# IMU_MPU9250.net
KiCad netlist of a schematic drawn in Altium Designer
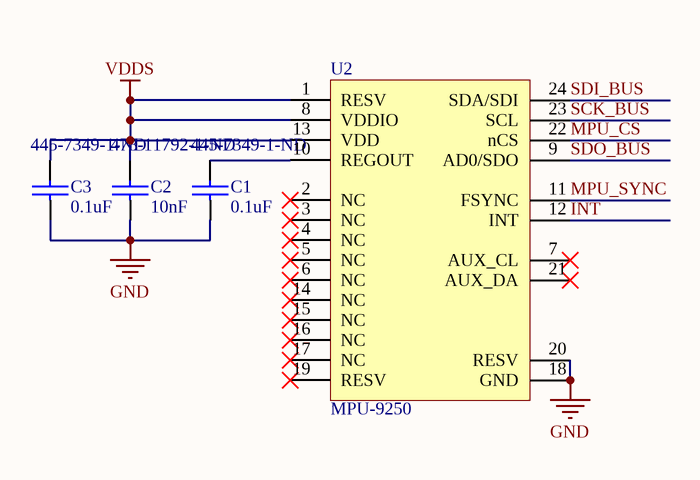
[diagram p0: IMU_MPU9250.SchDoc]

(export (version "E")
  (design (tool "Eeschema 10.0.6"))
  (components
    (comp (ref "C1")
      (value "0.1uF")
      (footprint "0402[IMP]")
      (fields (field (name "VOLTAGE") "CMAX") (field (name "SUPPLIER PART NUMBER 1") "445-7349-1-ND"))
      (libsource (lib "Biosense_Altium_Library") (part "CAPACITOR"))
    )
    (comp (ref "C2")
      (value "10nF")
      (footprint "0402[IMP]")
      (fields (field (name "VOLTAGE") "CMAX") (field (name "SUPPLIER PART NUMBER 1") "478-11792-1-ND"))
      (libsource (lib "Biosense_Altium_Library") (part "CAPACITOR"))
    )
    (comp (ref "C3")
      (value "0.1uF")
      (footprint "0402[IMP]")
      (fields (field (name "VOLTAGE") "CMAX") (field (name "SUPPLIER PART NUMBER 1") "445-7349-1-ND"))
      (libsource (lib "Biosense_Altium_Library") (part "CAPACITOR"))
    )
    (comp (ref "U2")
      (value "MPU-9250")
      (footprint "QFN-24-3mmx3mm")
      (libsource (lib "Biosense_Altium_Library") (part "MPU-9250"))
    )
  )
  (nets
    (net (code "1") (name "/INT") (class "Default")
      (node (ref "U2") (pin "12") (pinfunction "INT_12") (pintype "passive"))
    )
    (net (code "2") (name "/MPU_CS") (class "Default")
      (node (ref "U2") (pin "22") (pinfunction "nCS_22") (pintype "passive"))
    )
    (net (code "3") (name "/MPU_SYNC") (class "Default")
      (node (ref "U2") (pin "11") (pinfunction "FSYNC_11") (pintype "passive"))
    )
    (net (code "4") (name "/SCK_BUS") (class "Default")
      (node (ref "U2") (pin "23") (pinfunction "SCL_23") (pintype "passive"))
    )
    (net (code "5") (name "/SDI_BUS") (class "Default")
      (node (ref "U2") (pin "24") (pinfunction "SDA/SDI_24") (pintype "passive"))
    )
    (net (code "6") (name "/SDO_BUS") (class "Default")
      (node (ref "U2") (pin "9") (pinfunction "AD0/SDO_9") (pintype "passive"))
    )
    (net (code "7") (name "GND") (class "Default")
      (node (ref "C1") (pin "2") (pinfunction "2_2") (pintype "passive"))
      (node (ref "C2") (pin "2") (pinfunction "2_2") (pintype "passive"))
      (node (ref "C3") (pin "2") (pinfunction "2_2") (pintype "passive"))
      (node (ref "U2") (pin "18") (pinfunction "GND_18") (pintype "passive"))
      (node (ref "U2") (pin "20") (pinfunction "RESV_20") (pintype "passive"))
    )
    (net (code "8") (name "Net-(U2-REGOUT)") (class "Default")
      (node (ref "C1") (pin "1") (pinfunction "1_1") (pintype "passive"))
      (node (ref "U2") (pin "10") (pinfunction "REGOUT_10") (pintype "passive"))
    )
    (net (code "9") (name "VDDS") (class "Default")
      (node (ref "C2") (pin "1") (pinfunction "1_1") (pintype "passive"))
      (node (ref "C3") (pin "1") (pinfunction "1_1") (pintype "passive"))
      (node (ref "U2") (pin "1") (pinfunction "RESV_1") (pintype "passive"))
      (node (ref "U2") (pin "13") (pinfunction "VDD_13") (pintype "passive"))
      (node (ref "U2") (pin "8") (pinfunction "VDDIO_8") (pintype "passive"))
    )
    (net (code "10") (name "unconnected-(U2-AUX_CL-Pad7)") (class "Default")
      (node (ref "U2") (pin "7") (pinfunction "AUX_CL_7") (pintype "passive+no_connect"))
    )
    (net (code "11") (name "unconnected-(U2-AUX_DA-Pad21)") (class "Default")
      (node (ref "U2") (pin "21") (pinfunction "AUX_DA_21") (pintype "passive+no_connect"))
    )
    (net (code "12") (name "unconnected-(U2-NC-Pad2)") (class "Default")
      (node (ref "U2") (pin "2") (pinfunction "NC_2") (pintype "passive+no_connect"))
    )
    (net (code "13") (name "unconnected-(U2-NC-Pad3)") (class "Default")
      (node (ref "U2") (pin "3") (pinfunction "NC_3") (pintype "passive+no_connect"))
    )
    (net (code "14") (name "unconnected-(U2-NC-Pad4)") (class "Default")
      (node (ref "U2") (pin "4") (pinfunction "NC_4") (pintype "passive+no_connect"))
    )
    (net (code "15") (name "unconnected-(U2-NC-Pad5)") (class "Default")
      (node (ref "U2") (pin "5") (pinfunction "NC_5") (pintype "passive+no_connect"))
    )
    (net (code "16") (name "unconnected-(U2-NC-Pad6)") (class "Default")
      (node (ref "U2") (pin "6") (pinfunction "NC_6") (pintype "passive+no_connect"))
    )
    (net (code "17") (name "unconnected-(U2-NC-Pad14)") (class "Default")
      (node (ref "U2") (pin "14") (pinfunction "NC_14") (pintype "passive+no_connect"))
    )
    (net (code "18") (name "unconnected-(U2-NC-Pad15)") (class "Default")
      (node (ref "U2") (pin "15") (pinfunction "NC_15") (pintype "passive+no_connect"))
    )
    (net (code "19") (name "unconnected-(U2-NC-Pad16)") (class "Default")
      (node (ref "U2") (pin "16") (pinfunction "NC_16") (pintype "passive+no_connect"))
    )
    (net (code "20") (name "unconnected-(U2-NC-Pad17)") (class "Default")
      (node (ref "U2") (pin "17") (pinfunction "NC_17") (pintype "passive+no_connect"))
    )
    (net (code "21") (name "unconnected-(U2-RESV-Pad19)") (class "Default")
      (node (ref "U2") (pin "19") (pinfunction "RESV_19") (pintype "passive+no_connect"))
    )
  )
)
